# CONTOR.net
KiCad netlist of a schematic drawn in Altium Designer
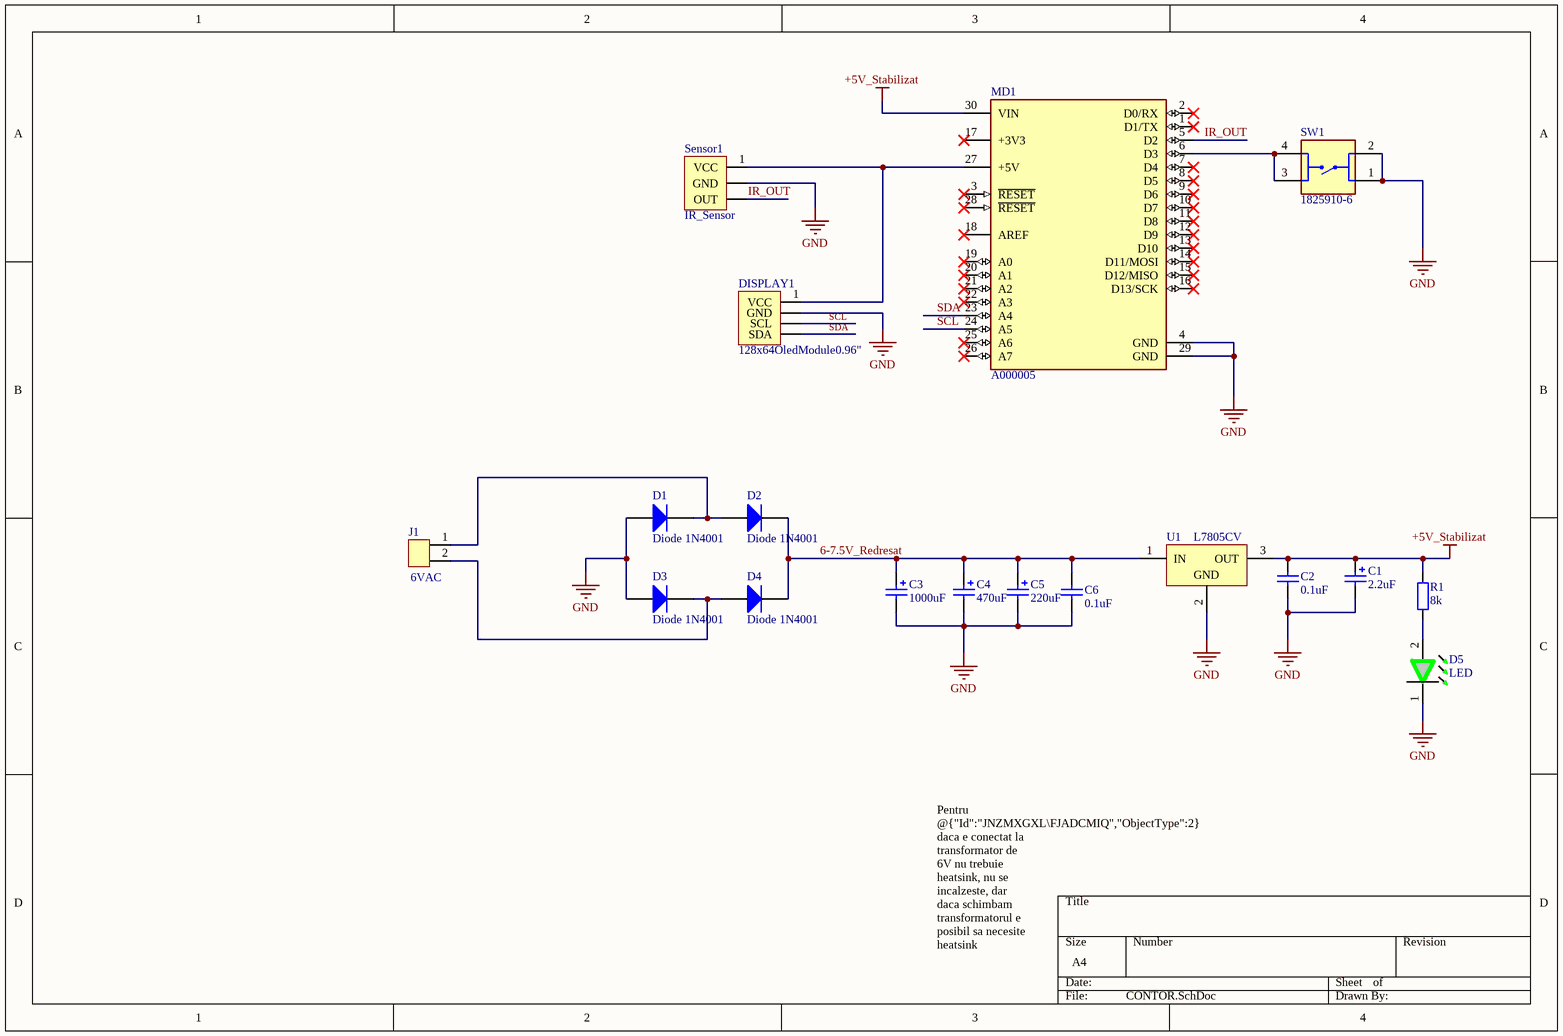
[diagram p0: CONTOR.SchDoc]

(export (version "E")
  (design (tool "Eeschema 10.0.6"))
  (components
    (comp (ref "C1")
      (value "2.2uF")
      (footprint "CAPPR 220uF 3mm_pin 8mmcase")
      (description "Polarized Capacitor (Radial)")
      (fields (field (name "PUBLISHER") "Altium Limited"))
      (libsource (lib "Schlib1") (part "2.2uF Cap"))
    )
    (comp (ref "C2")
      (value "0.1uF")
      (footprint "CAP104 0.1uF 3mm_pin")
      (description "104 cap")
      (libsource (lib "Schlib1") (part "CAP"))
    )
    (comp (ref "C3")
      (value "1000uF")
      (footprint "CAPPR 1000uF 5mm_pin 13mmcase")
      (description "Polarized Capacitor (Radial)")
      (fields (field (name "PUBLISHER") "Altium Limited"))
      (libsource (lib "Schlib1") (part "1000uF Cap"))
    )
    (comp (ref "C4")
      (value "470uF")
      (footprint "CAPPR 470uF 5mm_pin 10mmcase")
      (description "Polarized Capacitor (Radial)")
      (fields (field (name "PUBLISHER") "Altium Limited"))
      (libsource (lib "Schlib1") (part "470uF Cap"))
    )
    (comp (ref "C5")
      (value "220uF")
      (footprint "CAPPR 220uF 3mm_pin 8mmcase")
      (description "Polarized Capacitor (Radial)")
      (fields (field (name "PUBLISHER") "Altium Limited"))
      (libsource (lib "Schlib1") (part "220uF Cap"))
    )
    (comp (ref "C6")
      (value "0.1uF")
      (footprint "CAP104 0.1uF 3mm_pin")
      (description "104 cap")
      (libsource (lib "Schlib1") (part "CAP"))
    )
    (comp (ref "D1")
      (value "Diode 1N4001")
      (footprint "DO-41")
      (description "1 Amp General Purpose Rectifier")
      (fields (field (name "PUBLISHER") "Altium Limited"))
      (libsource (lib "Miscellaneous Devices") (part "Diode 1N4001"))
    )
    (comp (ref "D2")
      (value "Diode 1N4001")
      (footprint "DO-41")
      (description "1 Amp General Purpose Rectifier")
      (fields (field (name "PUBLISHER") "Altium Limited"))
      (libsource (lib "Miscellaneous Devices") (part "Diode 1N4001"))
    )
    (comp (ref "D3")
      (value "Diode 1N4001")
      (footprint "DO-41")
      (description "1 Amp General Purpose Rectifier")
      (fields (field (name "PUBLISHER") "Altium Limited"))
      (libsource (lib "Miscellaneous Devices") (part "Diode 1N4001"))
    )
    (comp (ref "D4")
      (value "Diode 1N4001")
      (footprint "DO-41")
      (description "1 Amp General Purpose Rectifier")
      (fields (field (name "PUBLISHER") "Altium Limited"))
      (libsource (lib "Miscellaneous Devices") (part "Diode 1N4001"))
    )
    (comp (ref "D5") (value "LED") (footprint "LED") (libsource (lib "Schlib1") (part "LED")))
    (comp (ref "DISPLAY1")
      (value "128x64OledModule0.96\"")
      (footprint "Oled Display")
      (description "OLED 4 Pin 128*64 Display Module 0.96” Blue Color")
      (libsource (lib "Schlib1") (part "0.96INCH_OLED_DISPLAY"))
    )
    (comp (ref "J1")
      (value "6VAC")
      (footprint "HDR_1X2_TE")
      (description "Connector, 2-Ports")
      (libsource (lib "Schlib1") (part "CON_1x2"))
    )
    (comp (ref "MD1")
      (value "A000005")
      (footprint "FP-A000005-MFG")
      (description "ARDUINO NANO ATMEGA328 EVAL BRD")
      (libsource (lib "Altium Content Vault") (part "d190c066e99afd1c6882cf92e11b2cc"))
    )
    (comp (ref "R1")
      (value "8k")
      (footprint "Resistor_1/4W")
      (description "0.25W,Axial")
      (libsource (lib "Schlib1") (part "Resistor 0.25W 5mm"))
    )
    (comp (ref "Sensor1")
      (value "IR_Sensor")
      (footprint "SENSOR IR")
      (description "IR_SENSOR")
      (libsource (lib "Schlib1") (part "IR_Sensor"))
    )
    (comp (ref "SW1")
      (value "1825910-6")
      (footprint "SW_1825910-6-4")
      (description "Switch Push Button OFF (ON) SPST Round Button 0.05A 24VDC Momentary Contact PC Pins Thru-Hole")
      (fields (field (name "MF") "TE Connectivity") (field (name "DIGI-KEY_PART_NUMBER") "450-1650-ND"))
      (libsource (lib "Schlib1") (part "1825910-6"))
    )
    (comp (ref "U1")
      (value "L7805CV")
      (footprint "TO220")
      (description "Positive Voltage Regulator, 5V, 3-Pin TO-220")
      (libsource (lib "Altium Content Vault") (part "PM-REG-L4940-SIL3"))
    )
  )
  (nets
    (net (code "1") (name "+5V_Stabilizat") (class "Default")
      (node (ref "C1") (pin "1") (pinfunction "1_1") (pintype "passive"))
      (node (ref "C2") (pin "1") (pinfunction "1_1") (pintype "passive"))
      (node (ref "MD1") (pin "30") (pinfunction "VIN_30") (pintype "power_in"))
      (node (ref "R1") (pin "2") (pinfunction "2_2") (pintype "passive"))
      (node (ref "U1") (pin "3") (pinfunction "OUT_3") (pintype "power_in"))
    )
    (net (code "2") (name "/6-7.5V_Redresat") (class "Default")
      (node (ref "C3") (pin "1") (pinfunction "1_1") (pintype "passive"))
      (node (ref "C4") (pin "1") (pinfunction "1_1") (pintype "passive"))
      (node (ref "C5") (pin "1") (pinfunction "1_1") (pintype "passive"))
      (node (ref "C6") (pin "1") (pinfunction "1_1") (pintype "passive"))
      (node (ref "D2") (pin "2") (pinfunction "K_2") (pintype "passive"))
      (node (ref "D4") (pin "2") (pinfunction "K_2") (pintype "passive"))
      (node (ref "U1") (pin "1") (pinfunction "IN_1") (pintype "power_in"))
    )
    (net (code "3") (name "/IR_OUT") (class "Default")
      (node (ref "MD1") (pin "5") (pinfunction "D2_5") (pintype "bidirectional"))
      (node (ref "Sensor1") (pin "3") (pinfunction "OUT_3") (pintype "passive"))
    )
    (net (code "4") (name "/SCL") (class "Default")
      (node (ref "DISPLAY1") (pin "3") (pinfunction "SCL_3") (pintype "passive"))
      (node (ref "MD1") (pin "24") (pinfunction "A5_24") (pintype "bidirectional"))
    )
    (net (code "5") (name "/SDA") (class "Default")
      (node (ref "DISPLAY1") (pin "4") (pinfunction "SDA_4") (pintype "passive"))
      (node (ref "MD1") (pin "23") (pinfunction "A4_23") (pintype "bidirectional"))
    )
    (net (code "6") (name "GND") (class "Default")
      (node (ref "C1") (pin "2") (pinfunction "2_2") (pintype "passive"))
      (node (ref "C2") (pin "2") (pinfunction "2_2") (pintype "passive"))
      (node (ref "C3") (pin "2") (pinfunction "2_2") (pintype "passive"))
      (node (ref "C4") (pin "2") (pinfunction "2_2") (pintype "passive"))
      (node (ref "C5") (pin "2") (pinfunction "2_2") (pintype "passive"))
      (node (ref "C6") (pin "2") (pinfunction "2_2") (pintype "passive"))
      (node (ref "D1") (pin "1") (pinfunction "A_1") (pintype "passive"))
      (node (ref "D3") (pin "1") (pinfunction "A_1") (pintype "passive"))
      (node (ref "D5") (pin "1") (pinfunction "1_1") (pintype "passive"))
      (node (ref "DISPLAY1") (pin "2") (pinfunction "GND_2") (pintype "passive"))
      (node (ref "MD1") (pin "29") (pinfunction "GND_29") (pintype "power_in"))
      (node (ref "MD1") (pin "4") (pinfunction "GND_4") (pintype "power_in"))
      (node (ref "SW1") (pin "1") (pinfunction "1_1") (pintype "passive"))
      (node (ref "SW1") (pin "2") (pinfunction "2_2") (pintype "passive"))
      (node (ref "Sensor1") (pin "2") (pinfunction "GND_2") (pintype "passive"))
      (node (ref "U1") (pin "2") (pinfunction "GND_2") (pintype "power_in"))
    )
    (net (code "7") (name "Net-(D1-K)") (class "Default")
      (node (ref "D1") (pin "2") (pinfunction "K_2") (pintype "passive"))
      (node (ref "D2") (pin "1") (pinfunction "A_1") (pintype "passive"))
      (node (ref "J1") (pin "1") (pinfunction "1_1") (pintype "passive"))
    )
    (net (code "8") (name "Net-(D3-K)") (class "Default")
      (node (ref "D3") (pin "2") (pinfunction "K_2") (pintype "passive"))
      (node (ref "D4") (pin "1") (pinfunction "A_1") (pintype "passive"))
      (node (ref "J1") (pin "2") (pinfunction "2_2") (pintype "passive"))
    )
    (net (code "9") (name "Net-(D5-Pad2)") (class "Default")
      (node (ref "D5") (pin "2") (pinfunction "2_2") (pintype "passive"))
      (node (ref "R1") (pin "1") (pinfunction "1_1") (pintype "passive"))
    )
    (net (code "10") (name "Net-(DISPLAY1-VCC)") (class "Default")
      (node (ref "DISPLAY1") (pin "1") (pinfunction "VCC_1") (pintype "passive"))
      (node (ref "MD1") (pin "27") (pinfunction "+5V_27") (pintype "power_in"))
      (node (ref "Sensor1") (pin "1") (pinfunction "VCC_1") (pintype "passive"))
    )
    (net (code "11") (name "Net-(MD1-D3)") (class "Default")
      (node (ref "MD1") (pin "6") (pinfunction "D3_6") (pintype "bidirectional"))
      (node (ref "SW1") (pin "3") (pinfunction "3_3") (pintype "passive"))
      (node (ref "SW1") (pin "4") (pinfunction "4_4") (pintype "passive"))
    )
    (net (code "12") (name "unconnected-(MD1-+3V3-Pad17)") (class "Default")
      (node (ref "MD1") (pin "17") (pinfunction "+3V3_17") (pintype "power_in+no_connect"))
    )
    (net (code "13") (name "unconnected-(MD1-A0-Pad19)") (class "Default")
      (node (ref "MD1") (pin "19") (pinfunction "A0_19") (pintype "bidirectional+no_connect"))
    )
    (net (code "14") (name "unconnected-(MD1-A1-Pad20)") (class "Default")
      (node (ref "MD1") (pin "20") (pinfunction "A1_20") (pintype "bidirectional+no_connect"))
    )
    (net (code "15") (name "unconnected-(MD1-A2-Pad21)") (class "Default")
      (node (ref "MD1") (pin "21") (pinfunction "A2_21") (pintype "bidirectional+no_connect"))
    )
    (net (code "16") (name "unconnected-(MD1-A3-Pad22)") (class "Default")
      (node (ref "MD1") (pin "22") (pinfunction "A3_22") (pintype "bidirectional+no_connect"))
    )
    (net (code "17") (name "unconnected-(MD1-A6-Pad25)") (class "Default")
      (node (ref "MD1") (pin "25") (pinfunction "A6_25") (pintype "bidirectional+no_connect"))
    )
    (net (code "18") (name "unconnected-(MD1-A7-Pad26)") (class "Default")
      (node (ref "MD1") (pin "26") (pinfunction "A7_26") (pintype "bidirectional+no_connect"))
    )
    (net (code "19") (name "unconnected-(MD1-AREF-Pad18)") (class "Default")
      (node (ref "MD1") (pin "18") (pinfunction "AREF_18") (pintype "passive+no_connect"))
    )
    (net (code "20") (name "unconnected-(MD1-D0{slash}RX-Pad2)") (class "Default")
      (node (ref "MD1") (pin "2") (pinfunction "D0/RX_2") (pintype "bidirectional+no_connect"))
    )
    (net (code "21") (name "unconnected-(MD1-D1{slash}TX-Pad1)") (class "Default")
      (node (ref "MD1") (pin "1") (pinfunction "D1/TX_1") (pintype "bidirectional+no_connect"))
    )
    (net (code "22") (name "unconnected-(MD1-D4-Pad7)") (class "Default")
      (node (ref "MD1") (pin "7") (pinfunction "D4_7") (pintype "bidirectional+no_connect"))
    )
    (net (code "23") (name "unconnected-(MD1-D5-Pad8)") (class "Default")
      (node (ref "MD1") (pin "8") (pinfunction "D5_8") (pintype "bidirectional+no_connect"))
    )
    (net (code "24") (name "unconnected-(MD1-D6-Pad9)") (class "Default")
      (node (ref "MD1") (pin "9") (pinfunction "D6_9") (pintype "bidirectional+no_connect"))
    )
    (net (code "25") (name "unconnected-(MD1-D7-Pad10)") (class "Default")
      (node (ref "MD1") (pin "10") (pinfunction "D7_10") (pintype "bidirectional+no_connect"))
    )
    (net (code "26") (name "unconnected-(MD1-D8-Pad11)") (class "Default")
      (node (ref "MD1") (pin "11") (pinfunction "D8_11") (pintype "bidirectional+no_connect"))
    )
    (net (code "27") (name "unconnected-(MD1-D9-Pad12)") (class "Default")
      (node (ref "MD1") (pin "12") (pinfunction "D9_12") (pintype "bidirectional+no_connect"))
    )
    (net (code "28") (name "unconnected-(MD1-D10-Pad13)") (class "Default")
      (node (ref "MD1") (pin "13") (pinfunction "D10_13") (pintype "bidirectional+no_connect"))
    )
    (net (code "29") (name "unconnected-(MD1-D11{slash}MOSI-Pad14)") (class "Default")
      (node (ref "MD1") (pin "14") (pinfunction "D11/MOSI_14") (pintype "bidirectional+no_connect"))
    )
    (net (code "30") (name "unconnected-(MD1-D12{slash}MISO-Pad15)") (class "Default")
      (node (ref "MD1") (pin "15") (pinfunction "D12/MISO_15") (pintype "bidirectional+no_connect"))
    )
    (net (code "31") (name "unconnected-(MD1-D13{slash}SCK-Pad16)") (class "Default")
      (node (ref "MD1") (pin "16") (pinfunction "D13/SCK_16") (pintype "bidirectional+no_connect"))
    )
    (net (code "32") (name "unconnected-(MD1-~{RESET}-Pad3)") (class "Default")
      (node (ref "MD1") (pin "3") (pinfunction "~{RESET}_3") (pintype "input+no_connect"))
    )
    (net (code "33") (name "unconnected-(MD1-~{RESET}-Pad28)") (class "Default")
      (node (ref "MD1") (pin "28") (pinfunction "~{RESET}_28") (pintype "input+no_connect"))
    )
  )
)
